# design.net
KiCad netlist of a schematic drawn in Altium Designer
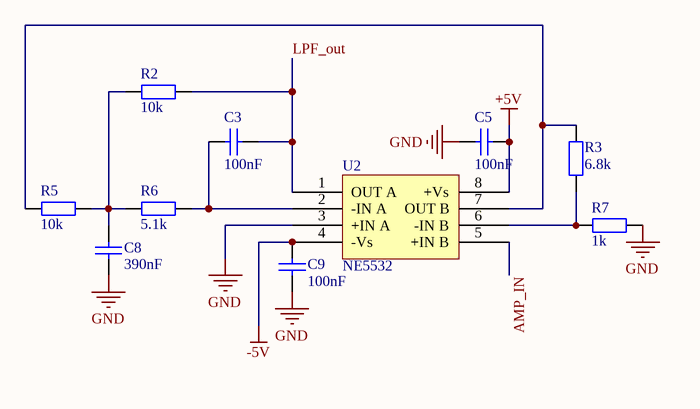
[diagram p0: 低通&放大.SchDoc]

(export (version "E")
  (design (tool "Eeschema 10.0.6"))
  (components
    (comp (ref "C3")
      (value "100nF")
      (footprint "LC-0805_C")
      (description "100nF��0805��50V,+/-10%")
      (libsource (lib "ECG") (part "Cap"))
    )
    (comp (ref "C5")
      (value "100nF")
      (footprint "LC-0805_C")
      (description "100nF��0805��50V,+/-10%")
      (libsource (lib "ECG") (part "Cap"))
    )
    (comp (ref "C8")
      (value "390nF")
      (footprint "LC-0805_C")
      (description "100nF��0805��50V,+/-10%")
      (libsource (lib "ECG") (part "Cap"))
    )
    (comp (ref "C9")
      (value "100nF")
      (footprint "LC-0805_C")
      (description "100nF��0805��50V,+/-10%")
      (libsource (lib "ECG") (part "Cap"))
    )
    (comp (ref "R2")
      (value "10k")
      (footprint "LC-0805_R")
      (description "10k��,0805,��5%")
      (libsource (lib "ECG") (part "R"))
    )
    (comp (ref "R3")
      (value "6.8k")
      (footprint "LC-0805_R")
      (description "10k��,0805,��5%")
      (libsource (lib "ECG") (part "R"))
    )
    (comp (ref "R5")
      (value "10k")
      (footprint "LC-0805_R")
      (description "10k��,0805,��5%")
      (libsource (lib "ECG") (part "R"))
    )
    (comp (ref "R6")
      (value "5.1k")
      (footprint "LC-0805_R")
      (description "10k��,0805,��5%")
      (libsource (lib "ECG") (part "R"))
    )
    (comp (ref "R7")
      (value "1k")
      (footprint "LC-0805_R")
      (description "10k��,0805,��5%")
      (libsource (lib "ECG") (part "R"))
    )
    (comp (ref "U2")
      (value "NE5532")
      (footprint "DIP-8")
      (description "NE5532��SO-8")
      (libsource (lib "ECG") (part "NE5532"))
    )
  )
  (nets
    (net (code "1") (name "+5V") (class "Default")
      (node (ref "C5") (pin "2") (pinfunction "2_2") (pintype "passive"))
      (node (ref "U2") (pin "8") (pinfunction "+Vs_8") (pintype "passive"))
    )
    (net (code "2") (name "-5V") (class "Default")
      (node (ref "C9") (pin "1") (pinfunction "1_1") (pintype "passive"))
      (node (ref "U2") (pin "4") (pinfunction "-Vs_4") (pintype "passive"))
    )
    (net (code "3") (name "/AMP_IN") (class "Default")
      (node (ref "U2") (pin "5") (pinfunction "+IN_B_5") (pintype "passive"))
    )
    (net (code "4") (name "/LPF_out") (class "Default")
      (node (ref "C3") (pin "2") (pinfunction "2_2") (pintype "passive"))
      (node (ref "R2") (pin "2") (pintype "passive"))
      (node (ref "U2") (pin "1") (pinfunction "OUT_A_1") (pintype "passive"))
    )
    (net (code "5") (name "GND") (class "Default")
      (node (ref "C5") (pin "1") (pinfunction "1_1") (pintype "passive"))
      (node (ref "C8") (pin "2") (pinfunction "2_2") (pintype "passive"))
      (node (ref "C9") (pin "2") (pinfunction "2_2") (pintype "passive"))
      (node (ref "R7") (pin "2") (pintype "passive"))
      (node (ref "U2") (pin "3") (pinfunction "+IN_A_3") (pintype "passive"))
    )
    (net (code "6") (name "Net-(C8-Pad1)") (class "Default")
      (node (ref "C8") (pin "1") (pinfunction "1_1") (pintype "passive"))
      (node (ref "R2") (pin "1") (pintype "passive"))
      (node (ref "R5") (pin "2") (pintype "passive"))
      (node (ref "R6") (pin "1") (pintype "passive"))
    )
    (net (code "7") (name "Net-(U2--IN_A)") (class "Default")
      (node (ref "C3") (pin "1") (pinfunction "1_1") (pintype "passive"))
      (node (ref "R6") (pin "2") (pintype "passive"))
      (node (ref "U2") (pin "2") (pinfunction "-IN_A_2") (pintype "passive"))
    )
    (net (code "8") (name "Net-(U2--IN_B)") (class "Default")
      (node (ref "R3") (pin "1") (pintype "passive"))
      (node (ref "R7") (pin "1") (pintype "passive"))
      (node (ref "U2") (pin "6") (pinfunction "-IN_B_6") (pintype "passive"))
    )
    (net (code "9") (name "Net-(U2-OUT_B)") (class "Default")
      (node (ref "R3") (pin "2") (pintype "passive"))
      (node (ref "R5") (pin "1") (pintype "passive"))
      (node (ref "U2") (pin "7") (pinfunction "OUT_B_7") (pintype "passive"))
    )
  )
)
